# SensorExt.net
KiCad netlist of a schematic drawn in Altium Designer
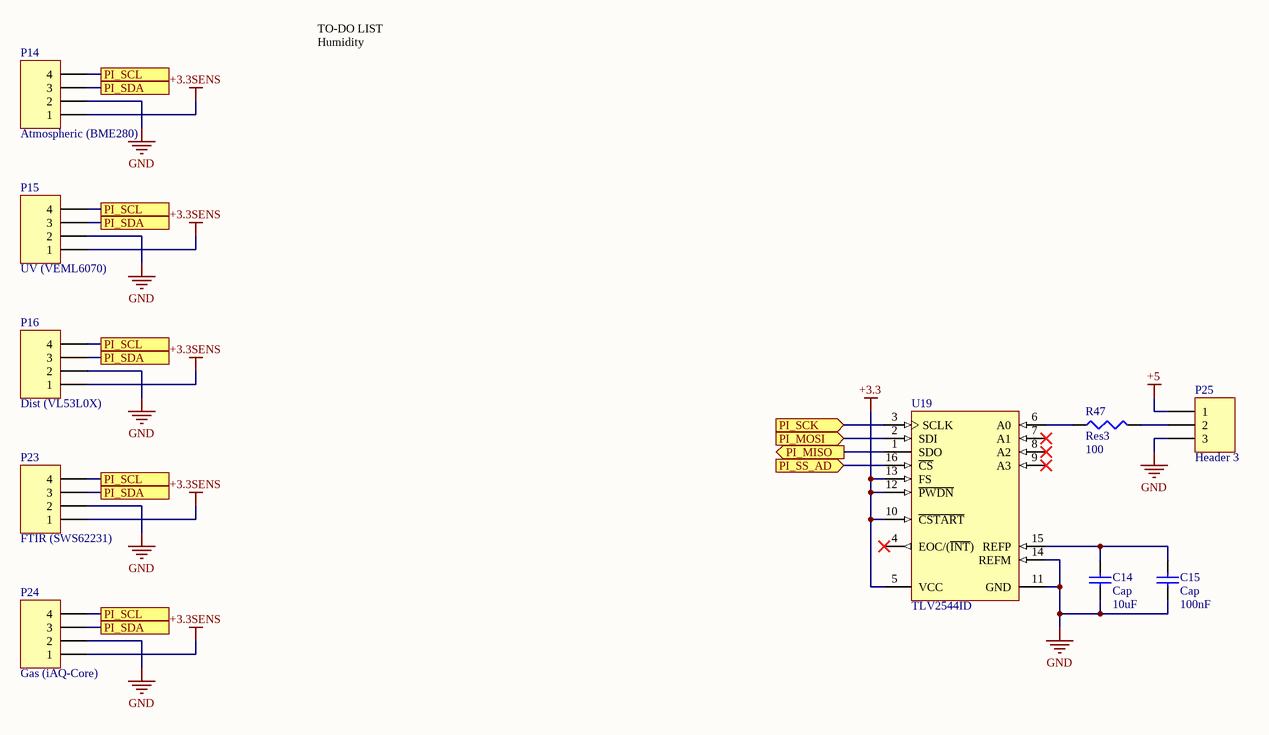
[diagram p0: SensorExt.SchDoc]

(export (version "E")
  (design (tool "Eeschema 10.0.6"))
  (components
    (comp (ref "C14")
      (value "Cap")
      (footprint "C0805")
      (description "Capacitor")
      (fields (field (name "ALTIUM_VALUE") "10uF") (field (name "PUBLISHER") "Altium Limited"))
      (libsource (lib "Miscellaneous Devices") (part "Cap"))
    )
    (comp (ref "C15")
      (value "Cap")
      (footprint "C0805")
      (description "Capacitor")
      (fields (field (name "ALTIUM_VALUE") "100nF") (field (name "PUBLISHER") "Altium Limited"))
      (libsource (lib "Miscellaneous Devices") (part "Cap"))
    )
    (comp (ref "P14")
      (value "Atmospheric (BME280)")
      (footprint "22-23-20x1-4pos")
      (description "Header, 4-Pin")
      (fields (field (name "PUBLISHER") "Altium Limited"))
      (libsource (lib "Miscellaneous Connectors") (part "Header 4"))
    )
    (comp (ref "P15")
      (value "UV (VEML6070)")
      (footprint "22-23-20x1-4pos")
      (description "Header, 4-Pin")
      (fields (field (name "PUBLISHER") "Altium Limited"))
      (libsource (lib "Miscellaneous Connectors") (part "Header 4"))
    )
    (comp (ref "P16")
      (value "Dist (VL53L0X)")
      (footprint "22-23-20x1-4pos")
      (description "Header, 4-Pin")
      (fields (field (name "PUBLISHER") "Altium Limited"))
      (libsource (lib "Miscellaneous Connectors") (part "Header 4"))
    )
    (comp (ref "P23")
      (value "FTIR (SWS62231)")
      (footprint "22-23-20x1-4pos")
      (description "Header, 4-Pin")
      (fields (field (name "PUBLISHER") "Altium Limited"))
      (libsource (lib "Miscellaneous Connectors") (part "Header 4"))
    )
    (comp (ref "P24")
      (value "Gas (iAQ-Core)")
      (footprint "22-23-20x1-4pos")
      (description "Header, 4-Pin")
      (fields (field (name "PUBLISHER") "Altium Limited"))
      (libsource (lib "Miscellaneous Connectors") (part "Header 4"))
    )
    (comp (ref "P25")
      (value "Header 3")
      (footprint "22-23-20x1-3pos")
      (description "Header, 3-Pin")
      (fields (field (name "PUBLISHER") "Altium Limited"))
      (libsource (lib "Miscellaneous Connectors") (part "Header 3"))
    )
    (comp (ref "R47")
      (value "Res3")
      (footprint "C0805")
      (description "Resistor")
      (fields (field (name "ALTIUM_VALUE") "100") (field (name "PUBLISHER") "Altium Limited"))
      (libsource (lib "Miscellaneous Devices") (part "Res3"))
    )
    (comp (ref "U19")
      (value "TLV2544ID")
      (footprint "TI-D16_M")
      (fields (field (name "MANUFACTURER") "Texas Instruments"))
      (libsource (lib "Altium Content Vault") (part "TI-TLX5X4XX16"))
    )
  )
  (nets
    (net (code "1") (name "+3.3") (class "Default")
      (node (ref "U19") (pin "10") (pinfunction "~{CSTART}_10") (pintype "input"))
      (node (ref "U19") (pin "12") (pinfunction "~{PWDN}_12") (pintype "input"))
      (node (ref "U19") (pin "13") (pinfunction "FS_13") (pintype "input"))
      (node (ref "U19") (pin "5") (pinfunction "VCC_5") (pintype "power_in"))
    )
    (net (code "2") (name "+3.3SENS") (class "Default")
      (node (ref "P14") (pin "1") (pinfunction "1_1") (pintype "passive"))
      (node (ref "P15") (pin "1") (pinfunction "1_1") (pintype "passive"))
      (node (ref "P16") (pin "1") (pinfunction "1_1") (pintype "passive"))
      (node (ref "P23") (pin "1") (pinfunction "1_1") (pintype "passive"))
      (node (ref "P24") (pin "1") (pinfunction "1_1") (pintype "passive"))
    )
    (net (code "3") (name "+5") (class "Default")
      (node (ref "P25") (pin "1") (pinfunction "1_1") (pintype "passive"))
    )
    (net (code "4") (name "/PI_MISO") (class "Default")
      (node (ref "U19") (pin "1") (pinfunction "SDO_1") (pintype "tri_state"))
    )
    (net (code "5") (name "/PI_MOSI") (class "Default")
      (node (ref "U19") (pin "2") (pinfunction "SDI_2") (pintype "input"))
    )
    (net (code "6") (name "/PI_SCK") (class "Default")
      (node (ref "U19") (pin "3") (pinfunction "SCLK_3") (pintype "input"))
    )
    (net (code "7") (name "/PI_SCL") (class "Default")
      (node (ref "P14") (pin "4") (pinfunction "4_4") (pintype "passive"))
      (node (ref "P15") (pin "4") (pinfunction "4_4") (pintype "passive"))
      (node (ref "P16") (pin "4") (pinfunction "4_4") (pintype "passive"))
      (node (ref "P23") (pin "4") (pinfunction "4_4") (pintype "passive"))
      (node (ref "P24") (pin "4") (pinfunction "4_4") (pintype "passive"))
    )
    (net (code "8") (name "/PI_SDA") (class "Default")
      (node (ref "P14") (pin "3") (pinfunction "3_3") (pintype "passive"))
      (node (ref "P15") (pin "3") (pinfunction "3_3") (pintype "passive"))
      (node (ref "P16") (pin "3") (pinfunction "3_3") (pintype "passive"))
      (node (ref "P23") (pin "3") (pinfunction "3_3") (pintype "passive"))
      (node (ref "P24") (pin "3") (pinfunction "3_3") (pintype "passive"))
    )
    (net (code "9") (name "/PI_SS_AD") (class "Default")
      (node (ref "U19") (pin "16") (pinfunction "~{CS}_16") (pintype "input"))
    )
    (net (code "10") (name "GND") (class "Default")
      (node (ref "C14") (pin "1") (pinfunction "1_1") (pintype "passive"))
      (node (ref "C15") (pin "1") (pinfunction "1_1") (pintype "passive"))
      (node (ref "P14") (pin "2") (pinfunction "2_2") (pintype "passive"))
      (node (ref "P15") (pin "2") (pinfunction "2_2") (pintype "passive"))
      (node (ref "P16") (pin "2") (pinfunction "2_2") (pintype "passive"))
      (node (ref "P23") (pin "2") (pinfunction "2_2") (pintype "passive"))
      (node (ref "P24") (pin "2") (pinfunction "2_2") (pintype "passive"))
      (node (ref "P25") (pin "3") (pinfunction "3_3") (pintype "passive"))
      (node (ref "U19") (pin "11") (pinfunction "GND_11") (pintype "power_in"))
      (node (ref "U19") (pin "14") (pinfunction "REFM_14") (pintype "input"))
    )
    (net (code "11") (name "Net-(P25-Pad2)") (class "Default")
      (node (ref "P25") (pin "2") (pinfunction "2_2") (pintype "passive"))
      (node (ref "R47") (pin "2") (pinfunction "2_2") (pintype "passive"))
    )
    (net (code "12") (name "Net-(U19-A0)") (class "Default")
      (node (ref "R47") (pin "1") (pinfunction "1_1") (pintype "passive"))
      (node (ref "U19") (pin "6") (pinfunction "A0_6") (pintype "input"))
    )
    (net (code "13") (name "Net-(U19-REFP)") (class "Default")
      (node (ref "C14") (pin "2") (pinfunction "2_2") (pintype "passive"))
      (node (ref "C15") (pin "2") (pinfunction "2_2") (pintype "passive"))
      (node (ref "U19") (pin "15") (pinfunction "REFP_15") (pintype "input"))
    )
    (net (code "14") (name "unconnected-(U19-A1-Pad7)") (class "Default")
      (node (ref "U19") (pin "7") (pinfunction "A1_7") (pintype "input+no_connect"))
    )
    (net (code "15") (name "unconnected-(U19-A2-Pad8)") (class "Default")
      (node (ref "U19") (pin "8") (pinfunction "A2_8") (pintype "input+no_connect"))
    )
    (net (code "16") (name "unconnected-(U19-A3-Pad9)") (class "Default")
      (node (ref "U19") (pin "9") (pinfunction "A3_9") (pintype "input+no_connect"))
    )
    (net (code "17") (name "unconnected-(U19-EOC{slash}(~{INT})-Pad4)") (class "Default")
      (node (ref "U19") (pin "4") (pinfunction "EOC/(~{INT})_4") (pintype "output+no_connect"))
    )
  )
)
